# imu.net
KiCad netlist of a schematic drawn in Altium Designer
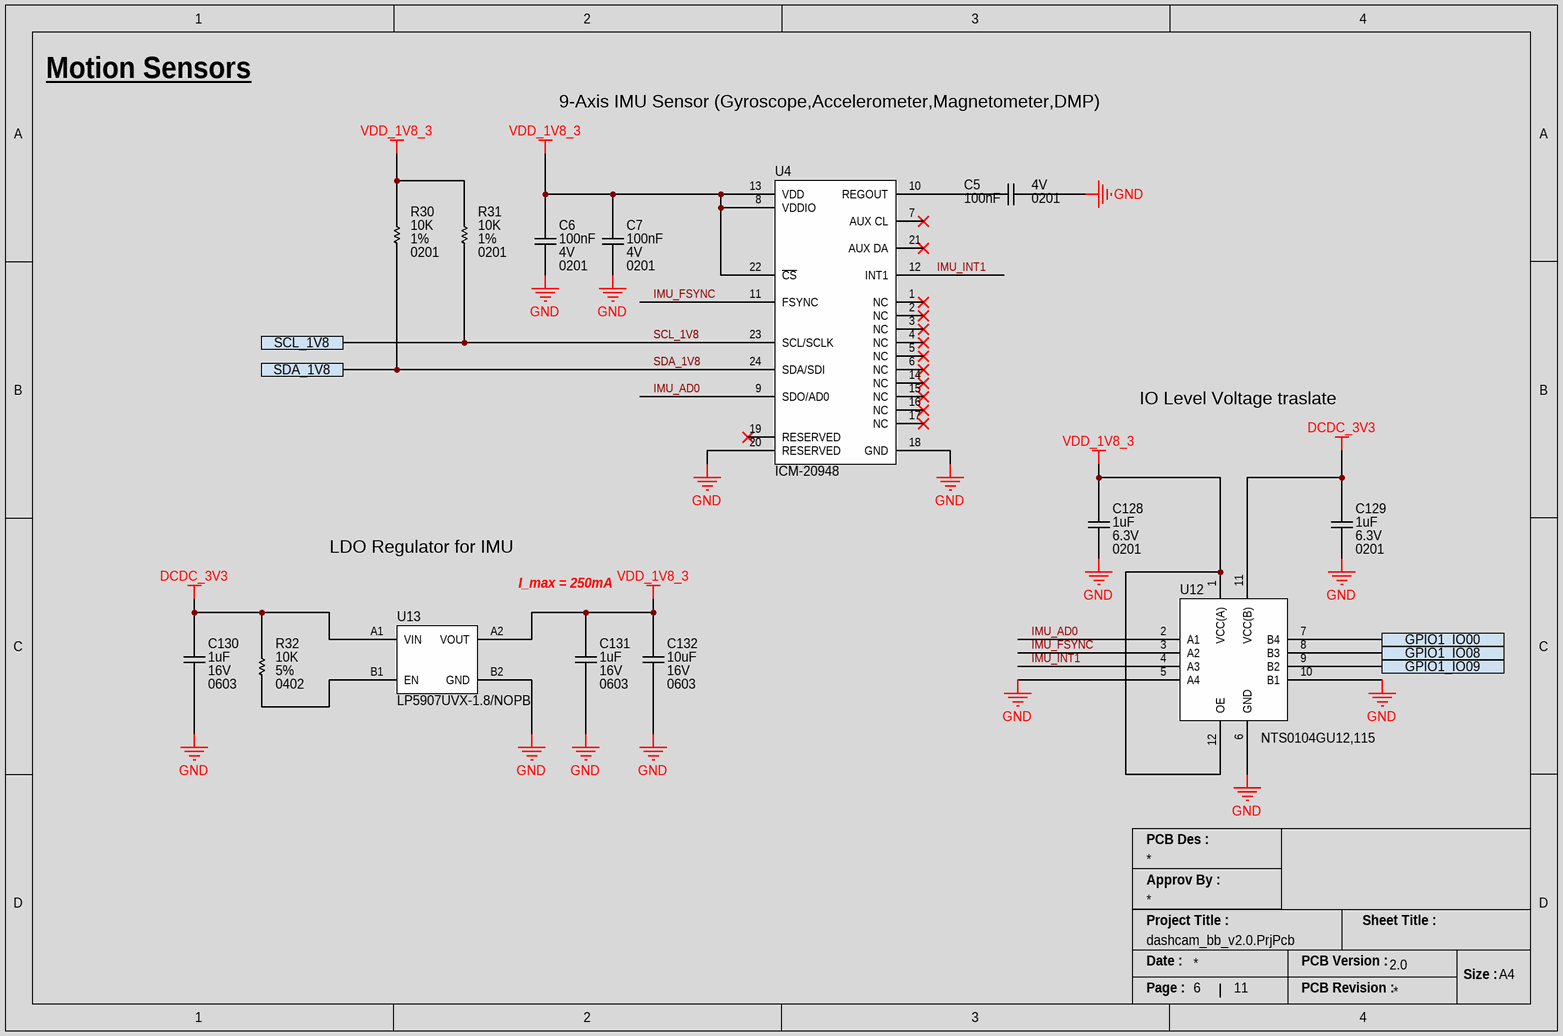
[diagram p0: imu.SchDoc]

(export (version "E")
  (design (tool "Eeschema 10.0.6"))
  (components
    (comp (ref "C5")
      (value "C0201C104K7PAC7867")
      (footprint "CAP_0201_CAPC0603X03N")
      (description "SMD Comm X5R 0201 (0603Metric) ceramic capacitor 0.024Lx0.012W 0.60mmx0.30mm X5R ±10% 0.1muF")
      (fields
        (field (name "MANUFACTURER") "KEMET")
        (field (name "TOLERANCE") "10%")
        (field (name "VOLTAGE RATING") "4V")
        (field (name "CAPACITANCE") "100nF")
        (field (name "CASE/PACKAGE") "0201")
      )
      (libsource (lib "Electronic Devices_LIB") (part "CAP_100NF_4V_X5R_0201"))
    )
    (comp (ref "C6")
      (value "C0201C104K7PAC7867")
      (footprint "CAP_0201_CAPC0603X03N")
      (description "SMD Comm X5R 0201 (0603Metric) ceramic capacitor 0.024Lx0.012W 0.60mmx0.30mm X5R ±10% 0.1muF")
      (fields
        (field (name "MANUFACTURER") "KEMET")
        (field (name "TOLERANCE") "10%")
        (field (name "VOLTAGE RATING") "4V")
        (field (name "CAPACITANCE") "100nF")
        (field (name "CASE/PACKAGE") "0201")
      )
      (libsource (lib "Electronic Devices_LIB") (part "CAP_100NF_4V_X5R_0201"))
    )
    (comp (ref "C7")
      (value "C0201C104K7PAC7867")
      (footprint "CAP_0201_CAPC0603X03N")
      (description "SMD Comm X5R 0201 (0603Metric) ceramic capacitor 0.024Lx0.012W 0.60mmx0.30mm X5R ±10% 0.1muF")
      (fields
        (field (name "MANUFACTURER") "KEMET")
        (field (name "TOLERANCE") "10%")
        (field (name "VOLTAGE RATING") "4V")
        (field (name "CAPACITANCE") "100nF")
        (field (name "CASE/PACKAGE") "0201")
      )
      (libsource (lib "Electronic Devices_LIB") (part "CAP_100NF_4V_X5R_0201"))
    )
    (comp (ref "C128")
      (value "02016D105MAT2A")
      (footprint "CAP_0201_CAPC0603X03N")
      (description "0201 1 uF 6.3 V ±20 % Tolerance X5R Surface Mount Multilayer Ceramic Capacitor")
      (fields
        (field (name "MANUFACTURER") "Kyocera AVX")
        (field (name "TOLERANCE") "20%")
        (field (name "VOLTAGE RATING (DC)") "6.3V")
        (field (name "CAPACITANCE") "1uF")
        (field (name "CASE/PACKAGE") "0201")
      )
      (libsource (lib "Electronic Devices_LIB") (part "CAP_1UF_6.3V_X5R_0201"))
    )
    (comp (ref "C129")
      (value "02016D105MAT2A")
      (footprint "CAP_0201_CAPC0603X03N")
      (description "0201 1 uF 6.3 V ±20 % Tolerance X5R Surface Mount Multilayer Ceramic Capacitor")
      (fields
        (field (name "MANUFACTURER") "Kyocera AVX")
        (field (name "TOLERANCE") "20%")
        (field (name "VOLTAGE RATING (DC)") "6.3V")
        (field (name "CAPACITANCE") "1uF")
        (field (name "CASE/PACKAGE") "0201")
      )
      (libsource (lib "Electronic Devices_LIB") (part "CAP_1UF_6.3V_X5R_0201"))
    )
    (comp (ref "C130")
      (value "CL10A105KO8NNNC")
      (footprint "CAP_0603_CAPC1608X08N")
      (description "CAP CER 1UF 16V X5R 0603")
      (fields
        (field (name "MANUFACTURER") "Samsung")
        (field (name "TOLERANCE") "10%")
        (field (name "VOLTAGE RATING") "16V")
        (field (name "CAPACITANCE") "1uF")
        (field (name "CASE/PACKAGE") "0603")
      )
      (libsource (lib "Electronic Devices_LIB") (part "CAP_1UF_16V_X5R_0603"))
    )
    (comp (ref "C131")
      (value "CL10A105KO8NNNC")
      (footprint "CAP_0603_CAPC1608X08N")
      (description "CAP CER 1UF 16V X5R 0603")
      (fields
        (field (name "MANUFACTURER") "Samsung")
        (field (name "TOLERANCE") "10%")
        (field (name "VOLTAGE RATING") "16V")
        (field (name "CAPACITANCE") "1uF")
        (field (name "CASE/PACKAGE") "0603")
      )
      (libsource (lib "Electronic Devices_LIB") (part "CAP_1UF_16V_X5R_0603"))
    )
    (comp (ref "C132")
      (value "GRM188R61C106MAALD")
      (footprint "CAP_0603_CAPC1608X08N")
      (description "0603 10 uF 16 V ±20% Tolerance X5R Multilayer Ceramic Chip Capacitor")
      (fields
        (field (name "MANUFACTURER") "Murata")
        (field (name "TOLERANCE") "20%")
        (field (name "VOLTAGE RATING") "16V")
        (field (name "CAPACITANCE") "10uF")
        (field (name "CASE/PACKAGE") "0603")
      )
      (libsource (lib "Electronic Devices_LIB") (part "CAP_10UF_16V_X5R_0603"))
    )
    (comp (ref "R30")
      (value "RC0201FR-0710KL")
      (footprint "RES_0201_RESC0603X02N")
      (description "SMD Chip Resistor, 10 kOhm, ± 1%, 50 mW, 0201 [0603 Metric], Thick Film, General Purpose")
      (fields
        (field (name "MANUFACTURER") "Yageo")
        (field (name "TOLERANCE") "1%")
        (field (name "RESISTANCE") "10K")
        (field (name "CASE CODE (IMPERIAL)") "0201")
      )
      (libsource (lib "Electronic Devices_LIB") (part "RES_10K_1/12W_1%_0201"))
    )
    (comp (ref "R31")
      (value "RC0201FR-0710KL")
      (footprint "RES_0201_RESC0603X02N")
      (description "SMD Chip Resistor, 10 kOhm, ± 1%, 50 mW, 0201 [0603 Metric], Thick Film, General Purpose")
      (fields
        (field (name "MANUFACTURER") "Yageo")
        (field (name "TOLERANCE") "1%")
        (field (name "RESISTANCE") "10K")
        (field (name "CASE CODE (IMPERIAL)") "0201")
      )
      (libsource (lib "Electronic Devices_LIB") (part "RES_10K_1/12W_1%_0201"))
    )
    (comp (ref "R32")
      (value "ERJ-2GEJ103X")
      (footprint "RES_0402_RESC1005X04N")
      (description "Res Thick Film 0402 10K Ohm 5% 1/10W ±200ppm/°C Molded SMD Punched Carrier T/R")
      (fields
        (field (name "MANUFACTURER") "Panasonic")
        (field (name "TOLERANCE") "5%")
        (field (name "RESISTANCE") "10K")
        (field (name "CASE/PACKAGE") "0402")
      )
      (libsource (lib "Electronic Devices_LIB") (part "RES_10K_5%_100mW_0402"))
    )
    (comp (ref "U4")
      (value "ICM-20948")
      (footprint "IC_IMU_TDK_InvenSense_0_IPC_A")
      (description "IMU (Inertial Measurement Unit), 9-Axis, Accelerometer, Gyroscope, Compass")
      (fields (field (name "MANUFACTURER") "TDK"))
      (libsource (lib "Electronic Devices_LIB") (part "IC_IMU_9AXIS_ICM-20948"))
    )
    (comp (ref "U12")
      (value "NTS0104GU12,115")
      (footprint "IC_LEVEL_TRASLATOR_XQFN12_0P4_1P8X2P1")
      (description "NTS0104 Series 50 Mbps Dual Supply 3-ST O-DRN Translating Transceiver- XQFN-12")
      (fields (field (name "MANUFACTURER") "NXP Semiconductors"))
      (libsource (lib "Electronic Devices_LIB") (part "IC_LEVEL_TRASLATOR_NTS0104GU12,115"))
    )
    (comp (ref "U13")
      (value "LP5907UVX-1.8/NOPB")
      (footprint "IC_REG_LDO_BGA4C35P2X2_71X71X40")
      (description "Low Dropout Regulators(LDO) Positive Fixed 200mV @ 250mA 5.5V 1.8V 250mA DSBGA-4 RoHS")
      (fields (field (name "MANUFACTURER") "Texas Instruments"))
      (libsource (lib "Electronic Devices_LIB") (part "IC_REG_LDO_1.8V_250mA_LP5907UVX-1.8/NOPB"))
    )
  )
  (nets
    (net (code "1") (name "/GPIO1_IO00") (class "Default")
      (node (ref "U12") (pin "7") (pinfunction "B4_7") (pintype "passive"))
    )
    (net (code "2") (name "/GPIO1_IO08") (class "Default")
      (node (ref "U12") (pin "8") (pinfunction "B3_8") (pintype "passive"))
    )
    (net (code "3") (name "/GPIO1_IO09") (class "Default")
      (node (ref "U12") (pin "9") (pinfunction "B2_9") (pintype "passive"))
    )
    (net (code "4") (name "/IMU_AD0") (class "Default")
      (node (ref "U12") (pin "2") (pinfunction "A1_2") (pintype "passive"))
      (node (ref "U4") (pin "9") (pinfunction "SDO/AD0_9") (pintype "passive"))
    )
    (net (code "5") (name "/IMU_FSYNC") (class "Default")
      (node (ref "U12") (pin "3") (pinfunction "A2_3") (pintype "passive"))
      (node (ref "U4") (pin "11") (pinfunction "FSYNC_11") (pintype "passive"))
    )
    (net (code "6") (name "/IMU_INT1") (class "Default")
      (node (ref "U12") (pin "4") (pinfunction "A3_4") (pintype "passive"))
      (node (ref "U4") (pin "12") (pinfunction "INT1_12") (pintype "passive"))
    )
    (net (code "7") (name "/SCL_1V8") (class "Default")
      (node (ref "R31") (pin "1") (pinfunction "1_1") (pintype "passive"))
      (node (ref "U4") (pin "23") (pinfunction "SCL/SCLK_23") (pintype "passive"))
    )
    (net (code "8") (name "/SDA_1V8") (class "Default")
      (node (ref "R30") (pin "1") (pinfunction "1_1") (pintype "passive"))
      (node (ref "U4") (pin "24") (pinfunction "SDA/SDI_24") (pintype "passive"))
    )
    (net (code "9") (name "DCDC_3V3") (class "Default")
      (node (ref "C129") (pin "2") (pinfunction "2_2") (pintype "passive"))
      (node (ref "C130") (pin "2") (pinfunction "2_2") (pintype "passive"))
      (node (ref "R32") (pin "2") (pinfunction "2_2") (pintype "passive"))
      (node (ref "U12") (pin "11") (pinfunction "VCC(B)_11") (pintype "passive"))
      (node (ref "U13") (pin "A1") (pinfunction "VIN_A1") (pintype "passive"))
    )
    (net (code "10") (name "GND") (class "Default")
      (node (ref "C128") (pin "1") (pinfunction "1_1") (pintype "passive"))
      (node (ref "C129") (pin "1") (pinfunction "1_1") (pintype "passive"))
      (node (ref "C130") (pin "1") (pinfunction "1_1") (pintype "passive"))
      (node (ref "C131") (pin "1") (pinfunction "1_1") (pintype "passive"))
      (node (ref "C132") (pin "1") (pinfunction "1_1") (pintype "passive"))
      (node (ref "C5") (pin "1") (pinfunction "1_1") (pintype "passive"))
      (node (ref "C6") (pin "1") (pinfunction "1_1") (pintype "passive"))
      (node (ref "C7") (pin "1") (pinfunction "1_1") (pintype "passive"))
      (node (ref "U12") (pin "10") (pinfunction "B1_10") (pintype "passive"))
      (node (ref "U12") (pin "5") (pinfunction "A4_5") (pintype "passive"))
      (node (ref "U12") (pin "6") (pinfunction "GND_6") (pintype "passive"))
      (node (ref "U13") (pin "B2") (pinfunction "GND_B2") (pintype "passive"))
      (node (ref "U4") (pin "18") (pinfunction "GND_18") (pintype "power_in"))
      (node (ref "U4") (pin "20") (pinfunction "RESERVED_20") (pintype "passive"))
    )
    (net (code "11") (name "Net-(U4-REGOUT)") (class "Default")
      (node (ref "C5") (pin "2") (pinfunction "2_2") (pintype "passive"))
      (node (ref "U4") (pin "10") (pinfunction "REGOUT_10") (pintype "passive"))
    )
    (net (code "12") (name "Net-(U13-EN)") (class "Default")
      (node (ref "R32") (pin "1") (pinfunction "1_1") (pintype "passive"))
      (node (ref "U13") (pin "B1") (pinfunction "EN_B1") (pintype "passive"))
    )
    (net (code "13") (name "VDD_1V8_3") (class "Default")
      (node (ref "C128") (pin "2") (pinfunction "2_2") (pintype "passive"))
      (node (ref "C131") (pin "2") (pinfunction "2_2") (pintype "passive"))
      (node (ref "C132") (pin "2") (pinfunction "2_2") (pintype "passive"))
      (node (ref "C6") (pin "2") (pinfunction "2_2") (pintype "passive"))
      (node (ref "C7") (pin "2") (pinfunction "2_2") (pintype "passive"))
      (node (ref "R30") (pin "2") (pinfunction "2_2") (pintype "passive"))
      (node (ref "R31") (pin "2") (pinfunction "2_2") (pintype "passive"))
      (node (ref "U12") (pin "1") (pinfunction "VCC(A)_1") (pintype "passive"))
      (node (ref "U12") (pin "12") (pinfunction "OE_12") (pintype "passive"))
      (node (ref "U13") (pin "A2") (pinfunction "VOUT_A2") (pintype "passive"))
      (node (ref "U4") (pin "13") (pinfunction "VDD_13") (pintype "power_in"))
      (node (ref "U4") (pin "22") (pinfunction "~{CS}_22") (pintype "passive"))
      (node (ref "U4") (pin "8") (pinfunction "VDDIO_8") (pintype "power_in"))
    )
    (net (code "14") (name "unconnected-(U4-AUX_CL-Pad7)") (class "Default")
      (node (ref "U4") (pin "7") (pinfunction "AUX_CL_7") (pintype "passive+no_connect"))
    )
    (net (code "15") (name "unconnected-(U4-AUX_DA-Pad21)") (class "Default")
      (node (ref "U4") (pin "21") (pinfunction "AUX_DA_21") (pintype "passive+no_connect"))
    )
    (net (code "16") (name "unconnected-(U4-NC-Pad1)") (class "Default")
      (node (ref "U4") (pin "1") (pinfunction "NC_1") (pintype "passive+no_connect"))
    )
    (net (code "17") (name "unconnected-(U4-NC-Pad2)") (class "Default")
      (node (ref "U4") (pin "2") (pinfunction "NC_2") (pintype "passive+no_connect"))
    )
    (net (code "18") (name "unconnected-(U4-NC-Pad3)") (class "Default")
      (node (ref "U4") (pin "3") (pinfunction "NC_3") (pintype "passive+no_connect"))
    )
    (net (code "19") (name "unconnected-(U4-NC-Pad4)") (class "Default")
      (node (ref "U4") (pin "4") (pinfunction "NC_4") (pintype "passive+no_connect"))
    )
    (net (code "20") (name "unconnected-(U4-NC-Pad5)") (class "Default")
      (node (ref "U4") (pin "5") (pinfunction "NC_5") (pintype "passive+no_connect"))
    )
    (net (code "21") (name "unconnected-(U4-NC-Pad6)") (class "Default")
      (node (ref "U4") (pin "6") (pinfunction "NC_6") (pintype "passive+no_connect"))
    )
    (net (code "22") (name "unconnected-(U4-NC-Pad14)") (class "Default")
      (node (ref "U4") (pin "14") (pinfunction "NC_14") (pintype "passive+no_connect"))
    )
    (net (code "23") (name "unconnected-(U4-NC-Pad15)") (class "Default")
      (node (ref "U4") (pin "15") (pinfunction "NC_15") (pintype "passive+no_connect"))
    )
    (net (code "24") (name "unconnected-(U4-NC-Pad16)") (class "Default")
      (node (ref "U4") (pin "16") (pinfunction "NC_16") (pintype "passive+no_connect"))
    )
    (net (code "25") (name "unconnected-(U4-NC-Pad17)") (class "Default")
      (node (ref "U4") (pin "17") (pinfunction "NC_17") (pintype "passive+no_connect"))
    )
    (net (code "26") (name "unconnected-(U4-RESERVED-Pad19)") (class "Default")
      (node (ref "U4") (pin "19") (pinfunction "RESERVED_19") (pintype "passive+no_connect"))
    )
  )
)
